# auxboxshield1_57.net
KiCad netlist of a schematic drawn in EAGLE
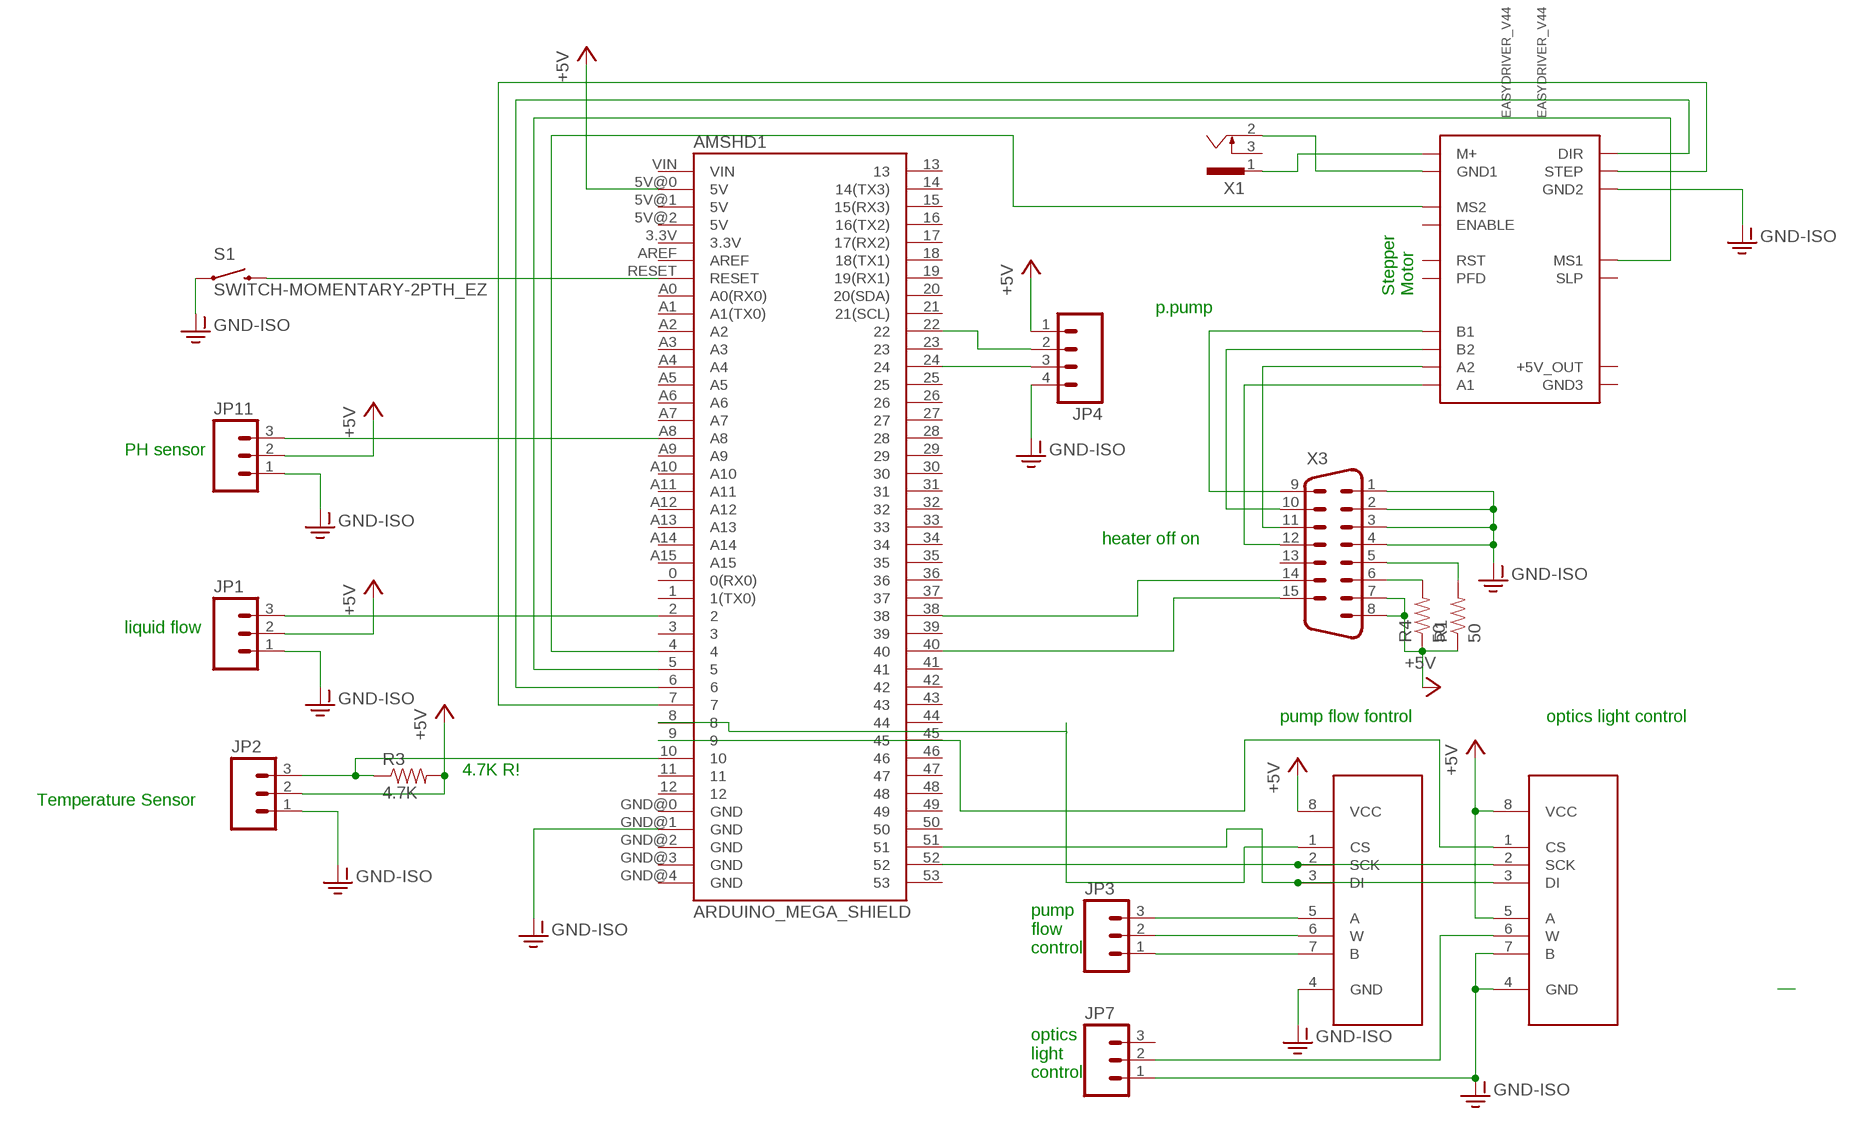
[diagram p0: schematic, sheet 1]

(export (version "E")
  (design (tool "Eeschema 10.0.6"))
  (components
    (comp (ref "AMSHD1")
      (value "ARDUINO_MEGA_SHIELD")
      (footprint "eagle-import:ARDUINO_MEGA_SHIELD")
      (libsource (lib "eagle-import") (part "ARDUINO_MEGA_SHIELD"))
    )
    (comp (ref "EASYDRIVER_V44")
      (value "EASYDRIVER_V44")
      (footprint "eagle-import:EASYDRIVER_V44")
      (libsource (lib "eagle-import") (part "EASYDRIVER_V44"))
    )
    (comp (ref "JP1")
      (value "M03POLAR")
      (footprint "eagle-import:MOLEX-1X3")
      (libsource (lib "eagle-import") (part "M03POLAR"))
    )
    (comp (ref "JP2")
      (value "M03POLAR")
      (footprint "eagle-import:MOLEX-1X3")
      (libsource (lib "eagle-import") (part "M03POLAR"))
    )
    (comp (ref "JP3")
      (value "M03POLAR")
      (footprint "eagle-import:MOLEX-1X3")
      (libsource (lib "eagle-import") (part "M03POLAR"))
    )
    (comp (ref "JP4")
      (value "M04POLAR")
      (footprint "eagle-import:MOLEX-1X4")
      (libsource (lib "eagle-import") (part "M04POLAR"))
    )
    (comp (ref "JP7")
      (value "M03POLAR")
      (footprint "eagle-import:MOLEX-1X3")
      (libsource (lib "eagle-import") (part "M03POLAR"))
    )
    (comp (ref "JP11")
      (value "M03POLAR")
      (footprint "eagle-import:MOLEX-1X3")
      (libsource (lib "eagle-import") (part "M03POLAR"))
    )
    (comp (ref "R1")
      (value "50")
      (footprint "eagle-import:AXIAL-0.3")
      (libsource (lib "eagle-import") (part "10OHM-1/4W-5%(PTH)"))
    )
    (comp (ref "R3")
      (value "4.7K")
      (footprint "eagle-import:AXIAL-0.3")
      (libsource (lib "eagle-import") (part "10OHM-1/4W-5%(PTH)"))
    )
    (comp (ref "R4")
      (value "50")
      (footprint "eagle-import:AXIAL-0.3")
      (libsource (lib "eagle-import") (part "10OHM-1/4W-5%(PTH)"))
    )
    (comp (ref "S1")
      (value "SWITCH-MOMENTARY-2PTH_EZ")
      (footprint "eagle-import:TACTILE-PTH-EZ")
      (libsource (lib "eagle-import") (part "SWITCH-MOMENTARY-2PTH_EZ"))
    )
    (comp (ref "U1")
      (value "MCP41XXXDIL")
      (footprint "eagle-import:DIL-08")
      (libsource (lib "eagle-import") (part "MCP41XXXDIL"))
    )
    (comp (ref "U2")
      (value "MCP41XXXDIL")
      (footprint "eagle-import:DIL-08")
      (libsource (lib "eagle-import") (part "MCP41XXXDIL"))
    )
    (comp (ref "X1")
      (value "SCD-014A")
      (footprint "eagle-import:SCD-014-A")
      (libsource (lib "eagle-import") (part "SCD-014A"))
    )
    (comp (ref "X3")
      (value "M15V")
      (footprint "eagle-import:M15V")
      (libsource (lib "eagle-import") (part "M15V"))
    )
  )
  (nets
    (net (code "1") (name "+5V") (class "Default")
      (node (ref "AMSHD1") (pin "5V@0") (pinfunction "5V_5V@0") (pintype "bidirectional"))
      (node (ref "JP1") (pin "2") (pinfunction "2_2") (pintype "passive"))
      (node (ref "JP11") (pin "2") (pinfunction "2_2") (pintype "passive"))
      (node (ref "JP2") (pin "2") (pinfunction "2_2") (pintype "passive"))
      (node (ref "JP4") (pin "1") (pinfunction "1_1") (pintype "passive"))
      (node (ref "R1") (pin "P$1") (pinfunction "1_P$1") (pintype "passive"))
      (node (ref "R3") (pin "P$2") (pinfunction "2_P$2") (pintype "passive"))
      (node (ref "R4") (pin "P$1") (pinfunction "1_P$1") (pintype "passive"))
      (node (ref "U1") (pin "5") (pinfunction "A_5") (pintype "bidirectional"))
      (node (ref "U1") (pin "8") (pinfunction "VCC_8") (pintype "bidirectional"))
      (node (ref "U2") (pin "8") (pinfunction "VCC_8") (pintype "bidirectional"))
      (node (ref "X3") (pin "7") (pinfunction "7_7") (pintype "passive"))
      (node (ref "X3") (pin "8") (pinfunction "8_8") (pintype "passive"))
    )
    (net (code "2") (name "GND-ISO") (class "Default")
      (node (ref "AMSHD1") (pin "GND@1") (pinfunction "GND_GND@1") (pintype "bidirectional"))
      (node (ref "EASYDRIVER_V44") (pin "GND2") (pinfunction "GND2_GND2") (pintype "bidirectional"))
      (node (ref "JP1") (pin "1") (pinfunction "1_1") (pintype "passive"))
      (node (ref "JP11") (pin "1") (pinfunction "1_1") (pintype "passive"))
      (node (ref "JP2") (pin "1") (pinfunction "1_1") (pintype "passive"))
      (node (ref "JP4") (pin "4") (pinfunction "4_4") (pintype "passive"))
      (node (ref "JP7") (pin "1") (pinfunction "1_1") (pintype "passive"))
      (node (ref "S1") (pin "1") (pinfunction "1_1") (pintype "passive"))
      (node (ref "U1") (pin "4") (pinfunction "GND_4") (pintype "bidirectional"))
      (node (ref "U1") (pin "7") (pinfunction "B_7") (pintype "bidirectional"))
      (node (ref "U2") (pin "4") (pinfunction "GND_4") (pintype "bidirectional"))
      (node (ref "X3") (pin "1") (pinfunction "1_1") (pintype "passive"))
      (node (ref "X3") (pin "2") (pinfunction "2_2") (pintype "passive"))
      (node (ref "X3") (pin "3") (pinfunction "3_3") (pintype "passive"))
      (node (ref "X3") (pin "4") (pinfunction "4_4") (pintype "passive"))
    )
    (net (code "3") (name "Net-(AMSHD1-Pad2)") (class "Default")
      (node (ref "AMSHD1") (pin "2") (pinfunction "2_2") (pintype "bidirectional"))
      (node (ref "JP1") (pin "3") (pinfunction "3_3") (pintype "passive"))
    )
    (net (code "4") (name "Net-(AMSHD1-Pad4)") (class "Default")
      (node (ref "AMSHD1") (pin "4") (pinfunction "4_4") (pintype "bidirectional"))
      (node (ref "EASYDRIVER_V44") (pin "MS2") (pinfunction "MS2_MS2") (pintype "bidirectional"))
    )
    (net (code "5") (name "Net-(AMSHD1-Pad5)") (class "Default")
      (node (ref "AMSHD1") (pin "5") (pinfunction "5_5") (pintype "bidirectional"))
      (node (ref "EASYDRIVER_V44") (pin "MS1") (pinfunction "MS1_MS1") (pintype "bidirectional"))
    )
    (net (code "6") (name "Net-(AMSHD1-Pad6)") (class "Default")
      (node (ref "AMSHD1") (pin "6") (pinfunction "6_6") (pintype "bidirectional"))
      (node (ref "EASYDRIVER_V44") (pin "DIR") (pinfunction "DIR_DIR") (pintype "bidirectional"))
    )
    (net (code "7") (name "Net-(AMSHD1-Pad7)") (class "Default")
      (node (ref "AMSHD1") (pin "7") (pinfunction "7_7") (pintype "bidirectional"))
      (node (ref "EASYDRIVER_V44") (pin "STEP") (pinfunction "STEP_STEP") (pintype "bidirectional"))
    )
    (net (code "8") (name "Net-(AMSHD1-Pad22)") (class "Default")
      (node (ref "AMSHD1") (pin "22") (pinfunction "22_22") (pintype "bidirectional"))
      (node (ref "JP4") (pin "2") (pinfunction "2_2") (pintype "passive"))
    )
    (net (code "9") (name "Net-(AMSHD1-Pad24)") (class "Default")
      (node (ref "AMSHD1") (pin "24") (pinfunction "24_24") (pintype "bidirectional"))
      (node (ref "JP4") (pin "3") (pinfunction "3_3") (pintype "passive"))
    )
    (net (code "10") (name "Net-(AMSHD1-Pad38)") (class "Default")
      (node (ref "AMSHD1") (pin "38") (pinfunction "38_38") (pintype "bidirectional"))
      (node (ref "X3") (pin "14") (pinfunction "14_14") (pintype "passive"))
    )
    (net (code "11") (name "Net-(AMSHD1-Pad40)") (class "Default")
      (node (ref "AMSHD1") (pin "40") (pinfunction "40_40") (pintype "bidirectional"))
      (node (ref "X3") (pin "15") (pinfunction "15_15") (pintype "passive"))
    )
    (net (code "12") (name "Net-(AMSHD1-PadA8)") (class "Default")
      (node (ref "AMSHD1") (pin "A8") (pinfunction "A8_A8") (pintype "bidirectional"))
      (node (ref "JP11") (pin "3") (pinfunction "3_3") (pintype "passive"))
    )
    (net (code "13") (name "Net-(EASYDRIVER_V44-PadA1)") (class "Default")
      (node (ref "EASYDRIVER_V44") (pin "A1") (pinfunction "A1_A1") (pintype "bidirectional"))
      (node (ref "X3") (pin "12") (pinfunction "12_12") (pintype "passive"))
    )
    (net (code "14") (name "Net-(EASYDRIVER_V44-PadA2)") (class "Default")
      (node (ref "EASYDRIVER_V44") (pin "A2") (pinfunction "A2_A2") (pintype "bidirectional"))
      (node (ref "X3") (pin "11") (pinfunction "11_11") (pintype "passive"))
    )
    (net (code "15") (name "Net-(EASYDRIVER_V44-PadB1)") (class "Default")
      (node (ref "EASYDRIVER_V44") (pin "B1") (pinfunction "B1_B1") (pintype "bidirectional"))
      (node (ref "X3") (pin "9") (pinfunction "9_9") (pintype "passive"))
    )
    (net (code "16") (name "Net-(EASYDRIVER_V44-PadB2)") (class "Default")
      (node (ref "EASYDRIVER_V44") (pin "B2") (pinfunction "B2_B2") (pintype "bidirectional"))
      (node (ref "X3") (pin "10") (pinfunction "10_10") (pintype "passive"))
    )
    (net (code "17") (name "Net-(EASYDRIVER_V44-PadGND1)") (class "Default")
      (node (ref "EASYDRIVER_V44") (pin "GND1") (pinfunction "GND1_GND1") (pintype "bidirectional"))
      (node (ref "X1") (pin "2") (pinfunction "2_2") (pintype "passive"))
    )
    (net (code "18") (name "Net-(EASYDRIVER_V44-PadM+)") (class "Default")
      (node (ref "EASYDRIVER_V44") (pin "M+") (pinfunction "M+_M+") (pintype "bidirectional"))
      (node (ref "X1") (pin "1") (pinfunction "1_1") (pintype "passive"))
    )
    (net (code "19") (name "Net-(R1-2)") (class "Default")
      (node (ref "R1") (pin "P$2") (pinfunction "2_P$2") (pintype "passive"))
      (node (ref "X3") (pin "5") (pinfunction "5_5") (pintype "passive"))
    )
    (net (code "20") (name "Net-(R3-1)") (class "Default")
      (node (ref "AMSHD1") (pin "10") (pinfunction "10_10") (pintype "bidirectional"))
      (node (ref "JP2") (pin "3") (pinfunction "3_3") (pintype "passive"))
      (node (ref "R3") (pin "P$1") (pinfunction "1_P$1") (pintype "passive"))
    )
    (net (code "21") (name "Net-(R4-2)") (class "Default")
      (node (ref "R4") (pin "P$2") (pinfunction "2_P$2") (pintype "passive"))
      (node (ref "X3") (pin "6") (pinfunction "6_6") (pintype "passive"))
    )
    (net (code "22") (name "Net-(S1-2)") (class "Default")
      (node (ref "AMSHD1") (pin "RESET") (pinfunction "RESET_RESET") (pintype "bidirectional"))
      (node (ref "S1") (pin "3") (pinfunction "2_3") (pintype "passive"))
    )
    (net (code "23") (name "Net-(U1-CS)") (class "Default")
      (node (ref "AMSHD1") (pin "9") (pinfunction "9_9") (pintype "bidirectional"))
      (node (ref "U1") (pin "1") (pinfunction "CS_1") (pintype "bidirectional"))
    )
    (net (code "24") (name "Net-(U1-DI)") (class "Default")
      (node (ref "AMSHD1") (pin "51") (pinfunction "51_51") (pintype "bidirectional"))
      (node (ref "U1") (pin "3") (pinfunction "DI_3") (pintype "bidirectional"))
      (node (ref "U2") (pin "3") (pinfunction "DI_3") (pintype "bidirectional"))
    )
    (net (code "25") (name "Net-(U1-SCK)") (class "Default")
      (node (ref "AMSHD1") (pin "52") (pinfunction "52_52") (pintype "bidirectional"))
      (node (ref "U1") (pin "2") (pinfunction "SCK_2") (pintype "bidirectional"))
      (node (ref "U2") (pin "2") (pinfunction "SCK_2") (pintype "bidirectional"))
    )
    (net (code "26") (name "Net-(U1-W)") (class "Default")
      (node (ref "JP7") (pin "2") (pinfunction "2_2") (pintype "passive"))
      (node (ref "U1") (pin "6") (pinfunction "W_6") (pintype "bidirectional"))
    )
    (net (code "27") (name "Net-(U2-A)") (class "Default")
      (node (ref "JP3") (pin "3") (pinfunction "3_3") (pintype "passive"))
      (node (ref "U2") (pin "5") (pinfunction "A_5") (pintype "bidirectional"))
    )
    (net (code "28") (name "Net-(U2-B)") (class "Default")
      (node (ref "JP3") (pin "1") (pinfunction "1_1") (pintype "passive"))
      (node (ref "U2") (pin "7") (pinfunction "B_7") (pintype "bidirectional"))
    )
    (net (code "29") (name "Net-(U2-CS)") (class "Default")
      (node (ref "AMSHD1") (pin "8") (pinfunction "8_8") (pintype "bidirectional"))
      (node (ref "U2") (pin "1") (pinfunction "CS_1") (pintype "bidirectional"))
    )
    (net (code "30") (name "Net-(U2-W)") (class "Default")
      (node (ref "JP3") (pin "2") (pinfunction "2_2") (pintype "passive"))
      (node (ref "U2") (pin "6") (pinfunction "W_6") (pintype "bidirectional"))
    )
    (net (code "31") (name "unconnected-(AMSHD1-0(RX0)-Pad0)") (class "Default")
      (node (ref "AMSHD1") (pin "0") (pinfunction "0(RX0)_0") (pintype "bidirectional"))
    )
    (net (code "32") (name "unconnected-(AMSHD1-1(TX0)-Pad1)") (class "Default")
      (node (ref "AMSHD1") (pin "1") (pinfunction "1(TX0)_1") (pintype "bidirectional"))
    )
    (net (code "33") (name "unconnected-(AMSHD1-5V-Pad5V@1)") (class "Default")
      (node (ref "AMSHD1") (pin "5V@1") (pinfunction "5V_5V@1") (pintype "bidirectional"))
    )
    (net (code "34") (name "unconnected-(AMSHD1-5V-Pad5V@2)") (class "Default")
      (node (ref "AMSHD1") (pin "5V@2") (pinfunction "5V_5V@2") (pintype "bidirectional"))
    )
    (net (code "35") (name "unconnected-(AMSHD1-14(TX3)-Pad14)") (class "Default")
      (node (ref "AMSHD1") (pin "14") (pinfunction "14(TX3)_14") (pintype "bidirectional"))
    )
    (net (code "36") (name "unconnected-(AMSHD1-15(RX3)-Pad15)") (class "Default")
      (node (ref "AMSHD1") (pin "15") (pinfunction "15(RX3)_15") (pintype "bidirectional"))
    )
    (net (code "37") (name "unconnected-(AMSHD1-16(TX2)-Pad16)") (class "Default")
      (node (ref "AMSHD1") (pin "16") (pinfunction "16(TX2)_16") (pintype "bidirectional"))
    )
    (net (code "38") (name "unconnected-(AMSHD1-17(RX2)-Pad17)") (class "Default")
      (node (ref "AMSHD1") (pin "17") (pinfunction "17(RX2)_17") (pintype "bidirectional"))
    )
    (net (code "39") (name "unconnected-(AMSHD1-18(TX1)-Pad18)") (class "Default")
      (node (ref "AMSHD1") (pin "18") (pinfunction "18(TX1)_18") (pintype "bidirectional"))
    )
    (net (code "40") (name "unconnected-(AMSHD1-19(RX1)-Pad19)") (class "Default")
      (node (ref "AMSHD1") (pin "19") (pinfunction "19(RX1)_19") (pintype "bidirectional"))
    )
    (net (code "41") (name "unconnected-(AMSHD1-20(SDA)-Pad20)") (class "Default")
      (node (ref "AMSHD1") (pin "20") (pinfunction "20(SDA)_20") (pintype "bidirectional"))
    )
    (net (code "42") (name "unconnected-(AMSHD1-21(SCL)-Pad21)") (class "Default")
      (node (ref "AMSHD1") (pin "21") (pinfunction "21(SCL)_21") (pintype "bidirectional"))
    )
    (net (code "43") (name "unconnected-(AMSHD1-A0(RX0)-PadA0)") (class "Default")
      (node (ref "AMSHD1") (pin "A0") (pinfunction "A0(RX0)_A0") (pintype "bidirectional"))
    )
    (net (code "44") (name "unconnected-(AMSHD1-A1(TX0)-PadA1)") (class "Default")
      (node (ref "AMSHD1") (pin "A1") (pinfunction "A1(TX0)_A1") (pintype "bidirectional"))
    )
    (net (code "45") (name "unconnected-(AMSHD1-GND-PadGND@0)") (class "Default")
      (node (ref "AMSHD1") (pin "GND@0") (pinfunction "GND_GND@0") (pintype "bidirectional"))
    )
    (net (code "46") (name "unconnected-(AMSHD1-GND-PadGND@2)") (class "Default")
      (node (ref "AMSHD1") (pin "GND@2") (pinfunction "GND_GND@2") (pintype "bidirectional"))
    )
    (net (code "47") (name "unconnected-(AMSHD1-GND-PadGND@3)") (class "Default")
      (node (ref "AMSHD1") (pin "GND@3") (pinfunction "GND_GND@3") (pintype "bidirectional"))
    )
    (net (code "48") (name "unconnected-(AMSHD1-GND-PadGND@4)") (class "Default")
      (node (ref "AMSHD1") (pin "GND@4") (pinfunction "GND_GND@4") (pintype "bidirectional"))
    )
    (net (code "49") (name "unconnected-(AMSHD1-Pad3)") (class "Default")
      (node (ref "AMSHD1") (pin "3") (pinfunction "3_3") (pintype "bidirectional"))
    )
    (net (code "50") (name "unconnected-(AMSHD1-Pad3.3V)") (class "Default")
      (node (ref "AMSHD1") (pin "3.3V") (pinfunction "3.3V_3.3V") (pintype "bidirectional"))
    )
    (net (code "51") (name "unconnected-(AMSHD1-Pad11)") (class "Default")
      (node (ref "AMSHD1") (pin "11") (pinfunction "11_11") (pintype "bidirectional"))
    )
    (net (code "52") (name "unconnected-(AMSHD1-Pad12)") (class "Default")
      (node (ref "AMSHD1") (pin "12") (pinfunction "12_12") (pintype "bidirectional"))
    )
    (net (code "53") (name "unconnected-(AMSHD1-Pad13)") (class "Default")
      (node (ref "AMSHD1") (pin "13") (pinfunction "13_13") (pintype "bidirectional"))
    )
    (net (code "54") (name "unconnected-(AMSHD1-Pad23)") (class "Default")
      (node (ref "AMSHD1") (pin "23") (pinfunction "23_23") (pintype "bidirectional"))
    )
    (net (code "55") (name "unconnected-(AMSHD1-Pad25)") (class "Default")
      (node (ref "AMSHD1") (pin "25") (pinfunction "25_25") (pintype "bidirectional"))
    )
    (net (code "56") (name "unconnected-(AMSHD1-Pad26)") (class "Default")
      (node (ref "AMSHD1") (pin "26") (pinfunction "26_26") (pintype "bidirectional"))
    )
    (net (code "57") (name "unconnected-(AMSHD1-Pad27)") (class "Default")
      (node (ref "AMSHD1") (pin "27") (pinfunction "27_27") (pintype "bidirectional"))
    )
    (net (code "58") (name "unconnected-(AMSHD1-Pad28)") (class "Default")
      (node (ref "AMSHD1") (pin "28") (pinfunction "28_28") (pintype "bidirectional"))
    )
    (net (code "59") (name "unconnected-(AMSHD1-Pad29)") (class "Default")
      (node (ref "AMSHD1") (pin "29") (pinfunction "29_29") (pintype "bidirectional"))
    )
    (net (code "60") (name "unconnected-(AMSHD1-Pad30)") (class "Default")
      (node (ref "AMSHD1") (pin "30") (pinfunction "30_30") (pintype "bidirectional"))
    )
    (net (code "61") (name "unconnected-(AMSHD1-Pad31)") (class "Default")
      (node (ref "AMSHD1") (pin "31") (pinfunction "31_31") (pintype "bidirectional"))
    )
    (net (code "62") (name "unconnected-(AMSHD1-Pad32)") (class "Default")
      (node (ref "AMSHD1") (pin "32") (pinfunction "32_32") (pintype "bidirectional"))
    )
    (net (code "63") (name "unconnected-(AMSHD1-Pad33)") (class "Default")
      (node (ref "AMSHD1") (pin "33") (pinfunction "33_33") (pintype "bidirectional"))
    )
    (net (code "64") (name "unconnected-(AMSHD1-Pad34)") (class "Default")
      (node (ref "AMSHD1") (pin "34") (pinfunction "34_34") (pintype "bidirectional"))
    )
    (net (code "65") (name "unconnected-(AMSHD1-Pad35)") (class "Default")
      (node (ref "AMSHD1") (pin "35") (pinfunction "35_35") (pintype "bidirectional"))
    )
    (net (code "66") (name "unconnected-(AMSHD1-Pad36)") (class "Default")
      (node (ref "AMSHD1") (pin "36") (pinfunction "36_36") (pintype "bidirectional"))
    )
    (net (code "67") (name "unconnected-(AMSHD1-Pad37)") (class "Default")
      (node (ref "AMSHD1") (pin "37") (pinfunction "37_37") (pintype "bidirectional"))
    )
    (net (code "68") (name "unconnected-(AMSHD1-Pad39)") (class "Default")
      (node (ref "AMSHD1") (pin "39") (pinfunction "39_39") (pintype "bidirectional"))
    )
    (net (code "69") (name "unconnected-(AMSHD1-Pad41)") (class "Default")
      (node (ref "AMSHD1") (pin "41") (pinfunction "41_41") (pintype "bidirectional"))
    )
    (net (code "70") (name "unconnected-(AMSHD1-Pad42)") (class "Default")
      (node (ref "AMSHD1") (pin "42") (pinfunction "42_42") (pintype "bidirectional"))
    )
    (net (code "71") (name "unconnected-(AMSHD1-Pad43)") (class "Default")
      (node (ref "AMSHD1") (pin "43") (pinfunction "43_43") (pintype "bidirectional"))
    )
    (net (code "72") (name "unconnected-(AMSHD1-Pad44)") (class "Default")
      (node (ref "AMSHD1") (pin "44") (pinfunction "44_44") (pintype "bidirectional"))
    )
    (net (code "73") (name "unconnected-(AMSHD1-Pad45)") (class "Default")
      (node (ref "AMSHD1") (pin "45") (pinfunction "45_45") (pintype "bidirectional"))
    )
    (net (code "74") (name "unconnected-(AMSHD1-Pad46)") (class "Default")
      (node (ref "AMSHD1") (pin "46") (pinfunction "46_46") (pintype "bidirectional"))
    )
    (net (code "75") (name "unconnected-(AMSHD1-Pad47)") (class "Default")
      (node (ref "AMSHD1") (pin "47") (pinfunction "47_47") (pintype "bidirectional"))
    )
    (net (code "76") (name "unconnected-(AMSHD1-Pad48)") (class "Default")
      (node (ref "AMSHD1") (pin "48") (pinfunction "48_48") (pintype "bidirectional"))
    )
    (net (code "77") (name "unconnected-(AMSHD1-Pad49)") (class "Default")
      (node (ref "AMSHD1") (pin "49") (pinfunction "49_49") (pintype "bidirectional"))
    )
    (net (code "78") (name "unconnected-(AMSHD1-Pad50)") (class "Default")
      (node (ref "AMSHD1") (pin "50") (pinfunction "50_50") (pintype "bidirectional"))
    )
    (net (code "79") (name "unconnected-(AMSHD1-Pad53)") (class "Default")
      (node (ref "AMSHD1") (pin "53") (pinfunction "53_53") (pintype "bidirectional"))
    )
    (net (code "80") (name "unconnected-(AMSHD1-PadA2)") (class "Default")
      (node (ref "AMSHD1") (pin "A2") (pinfunction "A2_A2") (pintype "bidirectional"))
    )
    (net (code "81") (name "unconnected-(AMSHD1-PadA3)") (class "Default")
      (node (ref "AMSHD1") (pin "A3") (pinfunction "A3_A3") (pintype "bidirectional"))
    )
    (net (code "82") (name "unconnected-(AMSHD1-PadA4)") (class "Default")
      (node (ref "AMSHD1") (pin "A4") (pinfunction "A4_A4") (pintype "bidirectional"))
    )
    (net (code "83") (name "unconnected-(AMSHD1-PadA5)") (class "Default")
      (node (ref "AMSHD1") (pin "A5") (pinfunction "A5_A5") (pintype "bidirectional"))
    )
    (net (code "84") (name "unconnected-(AMSHD1-PadA6)") (class "Default")
      (node (ref "AMSHD1") (pin "A6") (pinfunction "A6_A6") (pintype "bidirectional"))
    )
    (net (code "85") (name "unconnected-(AMSHD1-PadA7)") (class "Default")
      (node (ref "AMSHD1") (pin "A7") (pinfunction "A7_A7") (pintype "bidirectional"))
    )
    (net (code "86") (name "unconnected-(AMSHD1-PadA9)") (class "Default")
      (node (ref "AMSHD1") (pin "A9") (pinfunction "A9_A9") (pintype "bidirectional"))
    )
    (net (code "87") (name "unconnected-(AMSHD1-PadA10)") (class "Default")
      (node (ref "AMSHD1") (pin "A10") (pinfunction "A10_A10") (pintype "bidirectional"))
    )
    (net (code "88") (name "unconnected-(AMSHD1-PadA11)") (class "Default")
      (node (ref "AMSHD1") (pin "A11") (pinfunction "A11_A11") (pintype "bidirectional"))
    )
    (net (code "89") (name "unconnected-(AMSHD1-PadA12)") (class "Default")
      (node (ref "AMSHD1") (pin "A12") (pinfunction "A12_A12") (pintype "bidirectional"))
    )
    (net (code "90") (name "unconnected-(AMSHD1-PadA13)") (class "Default")
      (node (ref "AMSHD1") (pin "A13") (pinfunction "A13_A13") (pintype "bidirectional"))
    )
    (net (code "91") (name "unconnected-(AMSHD1-PadA14)") (class "Default")
      (node (ref "AMSHD1") (pin "A14") (pinfunction "A14_A14") (pintype "bidirectional"))
    )
    (net (code "92") (name "unconnected-(AMSHD1-PadA15)") (class "Default")
      (node (ref "AMSHD1") (pin "A15") (pinfunction "A15_A15") (pintype "bidirectional"))
    )
    (net (code "93") (name "unconnected-(AMSHD1-PadAREF)") (class "Default")
      (node (ref "AMSHD1") (pin "AREF") (pinfunction "AREF_AREF") (pintype "bidirectional"))
    )
    (net (code "94") (name "unconnected-(AMSHD1-PadVIN)") (class "Default")
      (node (ref "AMSHD1") (pin "VIN") (pinfunction "VIN_VIN") (pintype "bidirectional"))
    )
    (net (code "95") (name "unconnected-(EASYDRIVER_V44-+5V_OUT-PadP$11)") (class "Default")
      (node (ref "EASYDRIVER_V44") (pin "P$11") (pinfunction "+5V_OUT_P$11") (pintype "bidirectional"))
    )
    (net (code "96") (name "unconnected-(EASYDRIVER_V44-PadENABLE)") (class "Default")
      (node (ref "EASYDRIVER_V44") (pin "ENABLE") (pinfunction "ENABLE_ENABLE") (pintype "bidirectional"))
    )
    (net (code "97") (name "unconnected-(EASYDRIVER_V44-PadGND3)") (class "Default")
      (node (ref "EASYDRIVER_V44") (pin "GND3") (pinfunction "GND3_GND3") (pintype "bidirectional"))
    )
    (net (code "98") (name "unconnected-(EASYDRIVER_V44-PadPFD)") (class "Default")
      (node (ref "EASYDRIVER_V44") (pin "PFD") (pinfunction "PFD_PFD") (pintype "bidirectional"))
    )
    (net (code "99") (name "unconnected-(EASYDRIVER_V44-PadRST)") (class "Default")
      (node (ref "EASYDRIVER_V44") (pin "RST") (pinfunction "RST_RST") (pintype "bidirectional"))
    )
    (net (code "100") (name "unconnected-(EASYDRIVER_V44-SLP-PadSLEEP)") (class "Default")
      (node (ref "EASYDRIVER_V44") (pin "SLEEP") (pinfunction "SLP_SLEEP") (pintype "bidirectional"))
    )
    (net (code "101") (name "unconnected-(JP7-Pad3)") (class "Default")
      (node (ref "JP7") (pin "3") (pinfunction "3_3") (pintype "passive"))
    )
    (net (code "102") (name "unconnected-(X1-Pad3)") (class "Default")
      (node (ref "X1") (pin "3") (pinfunction "3_3") (pintype "passive"))
    )
    (net (code "103") (name "unconnected-(X3-Pad13)") (class "Default")
      (node (ref "X3") (pin "13") (pinfunction "13_13") (pintype "passive"))
    )
  )
)
